# EvvGC_v1_2.net
KiCad netlist of a schematic drawn in Altium Designer
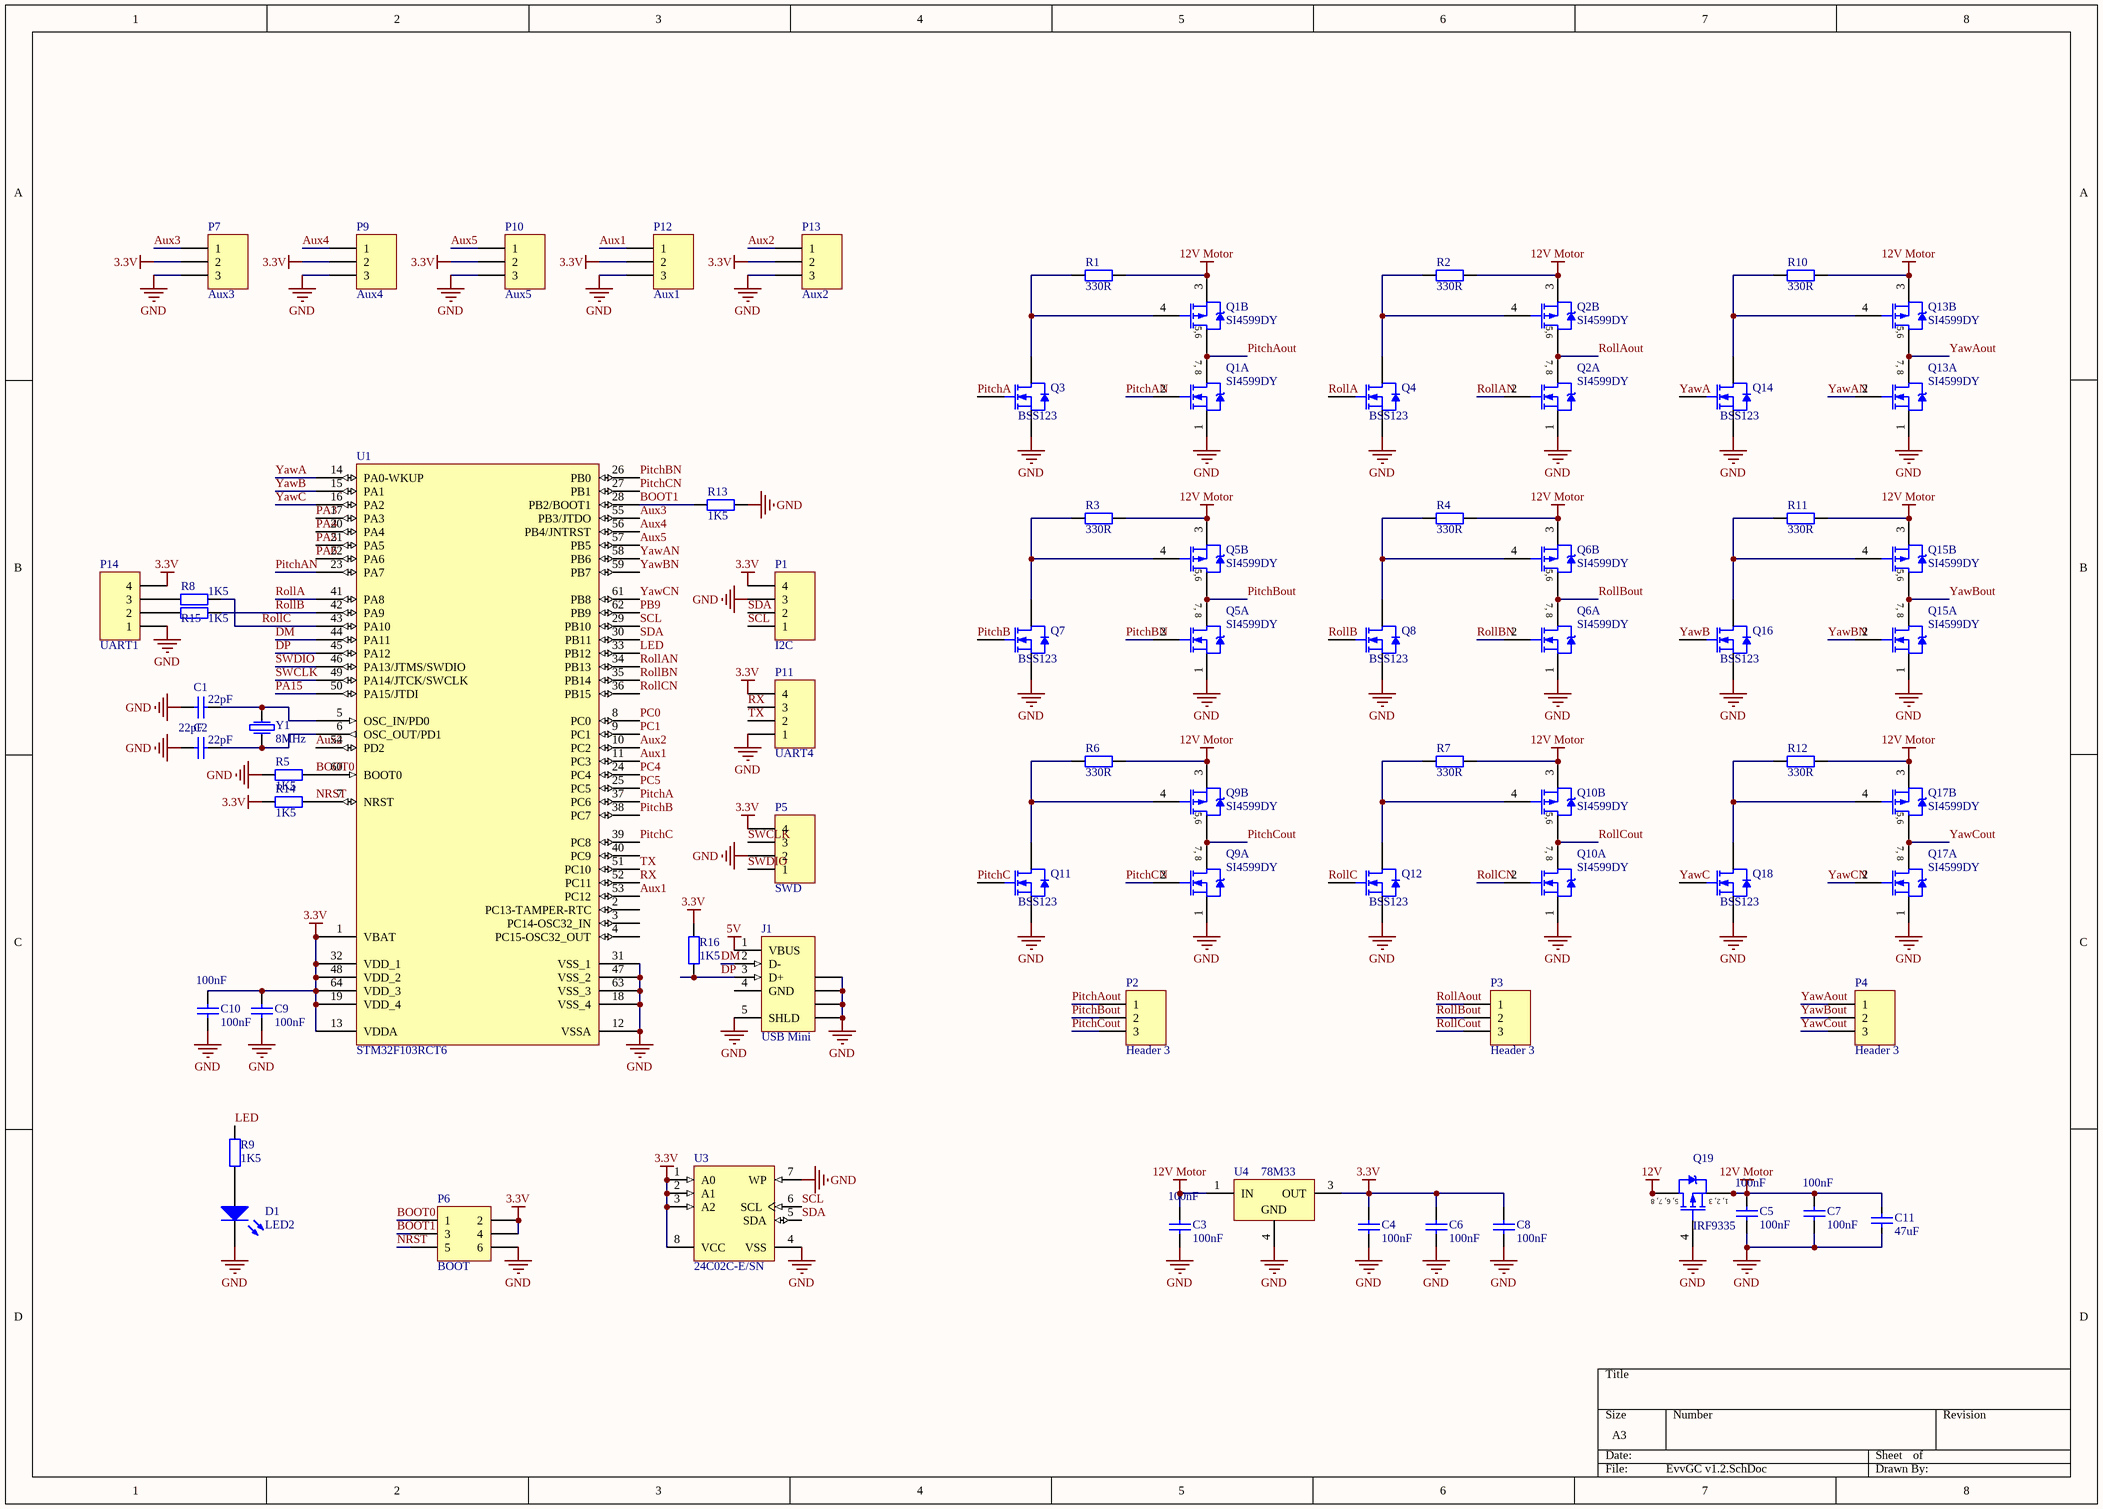
[diagram p0: EvvGC v1.2.SchDoc]

(export (version "E")
  (design (tool "Eeschema 10.0.6"))
  (components
    (comp (ref "C1")
      (value "22pF")
      (footprint "CAPC2012L")
      (description "Capacitor")
      (fields (field (name "PUBLISHER") "Altium Limited"))
      (libsource (lib "EMotus Components") (part "CAP0805"))
    )
    (comp (ref "C2")
      (value "22pF")
      (footprint "CAPC2012L")
      (description "Capacitor")
      (fields (field (name "ALTIUM_VALUE") "22pF") (field (name "PUBLISHER") "Altium Limited"))
      (libsource (lib "EMotus Components") (part "CAP0805"))
    )
    (comp (ref "C3")
      (value "100nF")
      (footprint "CAPC2012L")
      (description "Capacitor")
      (fields (field (name "ALTIUM_VALUE") "100nF") (field (name "PUBLISHER") "Altium Limited"))
      (libsource (lib "EMotus Components") (part "CAP0805"))
    )
    (comp (ref "C4")
      (value "100nF")
      (footprint "CAPC2012L")
      (description "Capacitor")
      (fields (field (name "PUBLISHER") "Altium Limited"))
      (libsource (lib "EMotus Components") (part "CAP0805"))
    )
    (comp (ref "C5")
      (value "100nF")
      (footprint "CAPC2012L")
      (description "Capacitor")
      (fields (field (name "ALTIUM_VALUE") "100nF") (field (name "PUBLISHER") "Altium Limited"))
      (libsource (lib "EMotus Components") (part "CAP0805"))
    )
    (comp (ref "C6")
      (value "100nF")
      (footprint "CAPC2012L")
      (description "Capacitor")
      (fields (field (name "PUBLISHER") "Altium Limited"))
      (libsource (lib "EMotus Components") (part "CAP0805"))
    )
    (comp (ref "C7")
      (value "100nF")
      (footprint "CAPC2012L")
      (description "Capacitor")
      (fields (field (name "ALTIUM_VALUE") "100nF") (field (name "PUBLISHER") "Altium Limited"))
      (libsource (lib "EMotus Components") (part "CAP0805"))
    )
    (comp (ref "C8")
      (value "100nF")
      (footprint "CAPC2012L")
      (description "Capacitor")
      (fields (field (name "PUBLISHER") "Altium Limited"))
      (libsource (lib "EMotus Components") (part "CAP0805"))
    )
    (comp (ref "C9")
      (value "100nF")
      (footprint "CAPC2012L")
      (description "Capacitor")
      (fields (field (name "PUBLISHER") "Altium Limited"))
      (libsource (lib "EMotus Components") (part "CAP0805"))
    )
    (comp (ref "C10")
      (value "100nF")
      (footprint "CAPC2012L")
      (description "Capacitor")
      (fields (field (name "ALTIUM_VALUE") "100nF") (field (name "PUBLISHER") "Altium Limited"))
      (libsource (lib "EMotus Components") (part "CAP0805"))
    )
    (comp (ref "C11")
      (value "47uF")
      (footprint "TC6032-2412")
      (description "Capacitor")
      (fields (field (name "PUBLISHER") "Altium Limited"))
      (libsource (lib "EMotus Components") (part "Cap"))
    )
    (comp (ref "D1")
      (value "LED2")
      (footprint "CAPC2012L")
      (description "Typical RED, GREEN, YELLOW, AMBER GaAs LED")
      (fields (field (name "PUBLISHER") "Altium Limited"))
      (libsource (lib "Miscellaneous Devices") (part "LED2"))
    )
    (comp (ref "J1")
      (value "USB Mini")
      (footprint "440247")
      (description "USB 2.0, Right Angle, SMT, B Type, Receptacle, 5 Position, Black")
      (fields (field (name "PUBLISHER") "Altium Limited"))
      (libsource (lib "AMP Serial Bus USB") (part "440247-2"))
    )
    (comp (ref "P1")
      (value "I2C")
      (footprint "HDR1X4")
      (description "Header, 4-Pin")
      (fields (field (name "PUBLISHER") "Altium Limited"))
      (libsource (lib "Miscellaneous Connectors") (part "Header 4"))
    )
    (comp (ref "P2")
      (value "Header 3")
      (footprint "HDR1X3")
      (description "Header, 3-Pin")
      (fields (field (name "PUBLISHER") "Altium Limited"))
      (libsource (lib "Miscellaneous Connectors") (part "Header 3"))
    )
    (comp (ref "P3")
      (value "Header 3")
      (footprint "HDR1X3")
      (description "Header, 3-Pin")
      (fields (field (name "PUBLISHER") "Altium Limited"))
      (libsource (lib "Miscellaneous Connectors") (part "Header 3"))
    )
    (comp (ref "P4")
      (value "Header 3")
      (footprint "HDR1X3")
      (description "Header, 3-Pin")
      (fields (field (name "PUBLISHER") "Altium Limited"))
      (libsource (lib "Miscellaneous Connectors") (part "Header 3"))
    )
    (comp (ref "P5")
      (value "SWD")
      (footprint "HDR1X4")
      (description "Header, 4-Pin")
      (fields (field (name "PUBLISHER") "Altium Limited"))
      (libsource (lib "Miscellaneous Connectors") (part "Header 4"))
    )
    (comp (ref "P6")
      (value "BOOT")
      (footprint "HDR2X3")
      (description "Header, 3-Pin, Dual row")
      (fields (field (name "PUBLISHER") "Altium Limited"))
      (libsource (lib "Miscellaneous Connectors") (part "Header 3X2"))
    )
    (comp (ref "P7")
      (value "Aux3")
      (footprint "HDR1X3")
      (description "Header, 3-Pin")
      (fields (field (name "PUBLISHER") "Altium Limited"))
      (libsource (lib "Miscellaneous Connectors") (part "Header 3"))
    )
    (comp (ref "P9")
      (value "Aux4")
      (footprint "HDR1X3")
      (description "Header, 3-Pin")
      (fields (field (name "PUBLISHER") "Altium Limited"))
      (libsource (lib "Miscellaneous Connectors") (part "Header 3"))
    )
    (comp (ref "P10")
      (value "Aux5")
      (footprint "HDR1X3")
      (description "Header, 3-Pin")
      (fields (field (name "PUBLISHER") "Altium Limited"))
      (libsource (lib "Miscellaneous Connectors") (part "Header 3"))
    )
    (comp (ref "P11")
      (value "UART4")
      (footprint "HDR1X4")
      (description "Header, 4-Pin")
      (fields (field (name "PUBLISHER") "Altium Limited"))
      (libsource (lib "Miscellaneous Connectors") (part "Header 4"))
    )
    (comp (ref "P12")
      (value "Aux1")
      (footprint "HDR1X3")
      (description "Header, 3-Pin")
      (fields (field (name "PUBLISHER") "Altium Limited"))
      (libsource (lib "Miscellaneous Connectors") (part "Header 3"))
    )
    (comp (ref "P13")
      (value "Aux2")
      (footprint "HDR1X3")
      (description "Header, 3-Pin")
      (fields (field (name "PUBLISHER") "Altium Limited"))
      (libsource (lib "Miscellaneous Connectors") (part "Header 3"))
    )
    (comp (ref "P14")
      (value "UART1")
      (footprint "HDR1X4")
      (description "Header, 4-Pin")
      (fields (field (name "PUBLISHER") "Altium Limited"))
      (libsource (lib "") (part "Header 4_1"))
    )
    (comp (ref "Q1")
      (value "SI4599DY")
      (footprint "SO-8_N")
      (description "HEXFET Power MOSFET")
      (fields (field (name "PUBLISHER") "Altium Limited"))
      (libsource (lib "VMU") (part "AUIRF7343"))
    )
    (comp (ref "Q2")
      (value "SI4599DY")
      (footprint "SO-8_N")
      (description "HEXFET Power MOSFET")
      (fields (field (name "PUBLISHER") "Altium Limited"))
      (libsource (lib "VMU") (part "AUIRF7343"))
    )
    (comp (ref "Q3")
      (value "BSS123")
      (footprint "SOT23_N_EM")
      (description "N-channel Enhancement Mode Field-effect Transistor")
      (fields (field (name "PUBLISHER") "Altium Limited"))
      (libsource (lib "EMotus Components") (part "2N7002"))
    )
    (comp (ref "Q4")
      (value "BSS123")
      (footprint "SOT23_N_EM")
      (description "N-channel Enhancement Mode Field-effect Transistor")
      (fields (field (name "PUBLISHER") "Altium Limited"))
      (libsource (lib "EMotus Components") (part "2N7002"))
    )
    (comp (ref "Q5")
      (value "SI4599DY")
      (footprint "SO-8_N")
      (description "HEXFET Power MOSFET")
      (fields (field (name "PUBLISHER") "Altium Limited"))
      (libsource (lib "VMU") (part "AUIRF7343"))
    )
    (comp (ref "Q6")
      (value "SI4599DY")
      (footprint "SO-8_N")
      (description "HEXFET Power MOSFET")
      (fields (field (name "PUBLISHER") "Altium Limited"))
      (libsource (lib "VMU") (part "AUIRF7343"))
    )
    (comp (ref "Q7")
      (value "BSS123")
      (footprint "SOT23_N_EM")
      (description "N-channel Enhancement Mode Field-effect Transistor")
      (fields (field (name "PUBLISHER") "Altium Limited"))
      (libsource (lib "EMotus Components") (part "2N7002"))
    )
    (comp (ref "Q8")
      (value "BSS123")
      (footprint "SOT23_N_EM")
      (description "N-channel Enhancement Mode Field-effect Transistor")
      (fields (field (name "PUBLISHER") "Altium Limited"))
      (libsource (lib "EMotus Components") (part "2N7002"))
    )
    (comp (ref "Q9")
      (value "SI4599DY")
      (footprint "SO-8_N")
      (description "HEXFET Power MOSFET")
      (fields (field (name "PUBLISHER") "Altium Limited"))
      (libsource (lib "VMU") (part "AUIRF7343"))
    )
    (comp (ref "Q10")
      (value "SI4599DY")
      (footprint "SO-8_N")
      (description "HEXFET Power MOSFET")
      (fields (field (name "PUBLISHER") "Altium Limited"))
      (libsource (lib "VMU") (part "AUIRF7343"))
    )
    (comp (ref "Q11")
      (value "BSS123")
      (footprint "SOT23_N_EM")
      (description "N-channel Enhancement Mode Field-effect Transistor")
      (fields (field (name "PUBLISHER") "Altium Limited"))
      (libsource (lib "EMotus Components") (part "2N7002"))
    )
    (comp (ref "Q12")
      (value "BSS123")
      (footprint "SOT23_N_EM")
      (description "N-channel Enhancement Mode Field-effect Transistor")
      (fields (field (name "PUBLISHER") "Altium Limited"))
      (libsource (lib "EMotus Components") (part "2N7002"))
    )
    (comp (ref "Q13")
      (value "SI4599DY")
      (footprint "SO-8_N")
      (description "HEXFET Power MOSFET")
      (fields (field (name "PUBLISHER") "Altium Limited"))
      (libsource (lib "VMU") (part "AUIRF7343"))
    )
    (comp (ref "Q14")
      (value "BSS123")
      (footprint "SOT23_N_EM")
      (description "N-channel Enhancement Mode Field-effect Transistor")
      (fields (field (name "PUBLISHER") "Altium Limited"))
      (libsource (lib "EMotus Components") (part "2N7002"))
    )
    (comp (ref "Q15")
      (value "SI4599DY")
      (footprint "SO-8_N")
      (description "HEXFET Power MOSFET")
      (fields (field (name "PUBLISHER") "Altium Limited"))
      (libsource (lib "VMU") (part "AUIRF7343"))
    )
    (comp (ref "Q16")
      (value "BSS123")
      (footprint "SOT23_N_EM")
      (description "N-channel Enhancement Mode Field-effect Transistor")
      (fields (field (name "PUBLISHER") "Altium Limited"))
      (libsource (lib "EMotus Components") (part "2N7002"))
    )
    (comp (ref "Q17")
      (value "SI4599DY")
      (footprint "SO-8_N")
      (description "HEXFET Power MOSFET")
      (fields (field (name "PUBLISHER") "Altium Limited"))
      (libsource (lib "VMU") (part "AUIRF7343"))
    )
    (comp (ref "Q18")
      (value "BSS123")
      (footprint "SOT23_N_EM")
      (description "N-channel Enhancement Mode Field-effect Transistor")
      (fields (field (name "PUBLISHER") "Altium Limited"))
      (libsource (lib "EMotus Components") (part "2N7002"))
    )
    (comp (ref "Q19")
      (value "IRF9335")
      (footprint "SO-8_N")
      (description "HEXFET Power MOSFET")
      (fields
        (field (name "MANUFACTURER") "International Rectifier")
        (field (name "PART NUMBER") "IRF9335PBF")
        (field (name "PUBLISHER") "Altium Limited")
      )
      (libsource (lib "IR Discrete MOSFET - Power") (part "IRF7404"))
    )
    (comp (ref "R1")
      (value "330R")
      (footprint "C0805")
      (description "Resistor")
      (fields (field (name "PUBLISHER") "Altium Limited"))
      (libsource (lib "My Altium Lib") (part "Res"))
    )
    (comp (ref "R2")
      (value "330R")
      (footprint "C0805")
      (description "Resistor")
      (fields (field (name "PUBLISHER") "Altium Limited"))
      (libsource (lib "My Altium Lib") (part "Res"))
    )
    (comp (ref "R3")
      (value "330R")
      (footprint "C0805")
      (description "Resistor")
      (fields (field (name "PUBLISHER") "Altium Limited"))
      (libsource (lib "My Altium Lib") (part "Res"))
    )
    (comp (ref "R4")
      (value "330R")
      (footprint "C0805")
      (description "Resistor")
      (fields (field (name "PUBLISHER") "Altium Limited"))
      (libsource (lib "My Altium Lib") (part "Res"))
    )
    (comp (ref "R5")
      (value "1K5")
      (footprint "RESC1608N")
      (description "RES 0603 1K5")
      (fields (field (name "TOLERANCE") "±5%"))
      (libsource (lib "Resistors") (part "RES 0603 330R"))
    )
    (comp (ref "R6")
      (value "330R")
      (footprint "C0805")
      (description "Resistor")
      (fields (field (name "PUBLISHER") "Altium Limited"))
      (libsource (lib "My Altium Lib") (part "Res"))
    )
    (comp (ref "R7")
      (value "330R")
      (footprint "C0805")
      (description "Resistor")
      (fields (field (name "PUBLISHER") "Altium Limited"))
      (libsource (lib "My Altium Lib") (part "Res"))
    )
    (comp (ref "R8")
      (value "1K5")
      (footprint "RESC1608N")
      (description "RES 0603 1K5")
      (fields (field (name "TOLERANCE") "±5%"))
      (libsource (lib "Resistors") (part "RES 0603 330R"))
    )
    (comp (ref "R9")
      (value "1K5")
      (footprint "RESC1608N")
      (description "RES 0603 1K5")
      (fields (field (name "TOLERANCE") "±5%"))
      (libsource (lib "") (part "RES 0603 330R_1"))
    )
    (comp (ref "R10")
      (value "330R")
      (footprint "C0805")
      (description "Resistor")
      (fields (field (name "PUBLISHER") "Altium Limited"))
      (libsource (lib "My Altium Lib") (part "Res"))
    )
    (comp (ref "R11")
      (value "330R")
      (footprint "C0805")
      (description "Resistor")
      (fields (field (name "PUBLISHER") "Altium Limited"))
      (libsource (lib "My Altium Lib") (part "Res"))
    )
    (comp (ref "R12")
      (value "330R")
      (footprint "C0805")
      (description "Resistor")
      (fields (field (name "PUBLISHER") "Altium Limited"))
      (libsource (lib "My Altium Lib") (part "Res"))
    )
    (comp (ref "R13")
      (value "1K5")
      (footprint "RESC1608N")
      (description "RES 0603 1K5")
      (fields (field (name "TOLERANCE") "±5%"))
      (libsource (lib "Resistors") (part "RES 0603 330R"))
    )
    (comp (ref "R14")
      (value "1K5")
      (footprint "RESC1608N")
      (description "RES 0603 1K5")
      (fields (field (name "TOLERANCE") "±5%"))
      (libsource (lib "Resistors") (part "RES 0603 330R"))
    )
    (comp (ref "R15")
      (value "1K5")
      (footprint "RESC1608N")
      (description "RES 0603 1K5")
      (fields (field (name "TOLERANCE") "±5%"))
      (libsource (lib "Resistors") (part "RES 0603 330R"))
    )
    (comp (ref "R16")
      (value "1K5")
      (footprint "RESC1608N")
      (description "RES 0603 1K5")
      (fields (field (name "TOLERANCE") "±5%"))
      (libsource (lib "") (part "RES 0603 330R_1"))
    )
    (comp (ref "U1")
      (value "STM32F103RCT6")
      (footprint "LQFP64_N")
      (description "STM32 ARM-based 32-bit MCU with 128 Kbytes Flash, 64-pin LQFP, Industrial Temperature")
      (fields (field (name "PUBLISHER") "Altium Limited"))
      (libsource (lib "ST Microcontroller 32-Bit STM32") (part "STM32F103RBT6"))
    )
    (comp (ref "U3")
      (value "24C02C-E/SN")
      (footprint "SOIC-SN8_N")
      (description "2Kbit, 400kHz, 5V, I2C Serial EEPROM, 8-Pin SOIC 150mil, Extended Temperature")
      (fields (field (name "PUBLISHER") "Altium Limited"))
      (libsource (lib "Microchip EEPROM I2C Serial") (part "24C02C-E/SN"))
    )
    (comp (ref "U4")
      (value "78M33")
      (footprint "TO-252")
      (description "Positive Voltage Regulator")
      (fields (field (name "PUBLISHER") "Altium Limited"))
      (libsource (lib "SMART LIB") (part "L78M05CDT"))
    )
    (comp (ref "Y1")
      (value "8MHz")
      (footprint "ABM3")
      (description "CRYSTAL 16M SMD5x3.2mm")
      (fields (field (name "MANUFACTURER") "ABRACON") (field (name "FARNELL PART NUMBER") "1611806"))
      (libsource (lib "elektromotus") (part "CRYSTAL 16M SMD5x3.2mm"))
    )
  )
  (nets
    (net (code "1") (name "/Aux1") (class "Default")
      (node (ref "P12") (pin "1") (pinfunction "1_1") (pintype "passive"))
      (node (ref "U1") (pin "11") (pinfunction "PC3_11") (pintype "bidirectional"))
      (node (ref "U1") (pin "53") (pinfunction "PC12_53") (pintype "bidirectional"))
    )
    (net (code "2") (name "/Aux2") (class "Default")
      (node (ref "P13") (pin "1") (pinfunction "1_1") (pintype "passive"))
      (node (ref "U1") (pin "10") (pinfunction "PC2_10") (pintype "bidirectional"))
      (node (ref "U1") (pin "54") (pinfunction "PD2_54") (pintype "bidirectional"))
    )
    (net (code "3") (name "/Aux3") (class "Default")
      (node (ref "P7") (pin "1") (pinfunction "1_1") (pintype "passive"))
      (node (ref "U1") (pin "55") (pinfunction "PB3/JTDO_55") (pintype "bidirectional"))
    )
    (net (code "4") (name "/Aux4") (class "Default")
      (node (ref "P9") (pin "1") (pinfunction "1_1") (pintype "passive"))
      (node (ref "U1") (pin "56") (pinfunction "PB4/JNTRST_56") (pintype "bidirectional"))
    )
    (net (code "5") (name "/Aux5") (class "Default")
      (node (ref "P10") (pin "1") (pinfunction "1_1") (pintype "passive"))
      (node (ref "U1") (pin "57") (pinfunction "PB5_57") (pintype "bidirectional"))
    )
    (net (code "6") (name "/BOOT0") (class "Default")
      (node (ref "P6") (pin "1") (pinfunction "1_1") (pintype "passive"))
      (node (ref "R5") (pin "1") (pinfunction "1_1") (pintype "passive"))
      (node (ref "U1") (pin "60") (pinfunction "BOOT0_60") (pintype "input"))
    )
    (net (code "7") (name "/BOOT1") (class "Default")
      (node (ref "P6") (pin "3") (pinfunction "3_3") (pintype "passive"))
      (node (ref "R13") (pin "2") (pinfunction "2_2") (pintype "passive"))
      (node (ref "U1") (pin "28") (pinfunction "PB2/BOOT1_28") (pintype "bidirectional"))
    )
    (net (code "8") (name "/DM") (class "Default")
      (node (ref "J1") (pin "2") (pinfunction "D-_2") (pintype "input"))
      (node (ref "U1") (pin "44") (pinfunction "PA11_44") (pintype "bidirectional"))
    )
    (net (code "9") (name "/DP") (class "Default")
      (node (ref "J1") (pin "3") (pinfunction "D+_3") (pintype "input"))
      (node (ref "R16") (pin "2") (pinfunction "2_2") (pintype "passive"))
      (node (ref "U1") (pin "45") (pinfunction "PA12_45") (pintype "bidirectional"))
    )
    (net (code "10") (name "/LED") (class "Default")
      (node (ref "R9") (pin "1") (pinfunction "1_1") (pintype "passive"))
      (node (ref "U1") (pin "33") (pinfunction "PB12_33") (pintype "bidirectional"))
    )
    (net (code "11") (name "/NRST") (class "Default")
      (node (ref "P6") (pin "5") (pinfunction "5_5") (pintype "passive"))
      (node (ref "R14") (pin "1") (pinfunction "1_1") (pintype "passive"))
      (node (ref "U1") (pin "7") (pinfunction "NRST_7") (pintype "bidirectional"))
    )
    (net (code "12") (name "/PA3") (class "Default")
      (node (ref "U1") (pin "17") (pinfunction "PA3_17") (pintype "bidirectional"))
    )
    (net (code "13") (name "/PA4") (class "Default")
      (node (ref "U1") (pin "20") (pinfunction "PA4_20") (pintype "bidirectional"))
    )
    (net (code "14") (name "/PA5") (class "Default")
      (node (ref "U1") (pin "21") (pinfunction "PA5_21") (pintype "bidirectional"))
    )
    (net (code "15") (name "/PA6") (class "Default")
      (node (ref "U1") (pin "22") (pinfunction "PA6_22") (pintype "bidirectional"))
    )
    (net (code "16") (name "/PA15") (class "Default")
      (node (ref "U1") (pin "50") (pinfunction "PA15/JTDI_50") (pintype "bidirectional"))
    )
    (net (code "17") (name "/PB9") (class "Default")
      (node (ref "U1") (pin "62") (pinfunction "PB9_62") (pintype "bidirectional"))
    )
    (net (code "18") (name "/PC0") (class "Default")
      (node (ref "U1") (pin "8") (pinfunction "PC0_8") (pintype "bidirectional"))
    )
    (net (code "19") (name "/PC1") (class "Default")
      (node (ref "U1") (pin "9") (pinfunction "PC1_9") (pintype "bidirectional"))
    )
    (net (code "20") (name "/PC4") (class "Default")
      (node (ref "U1") (pin "24") (pinfunction "PC4_24") (pintype "bidirectional"))
    )
    (net (code "21") (name "/PC5") (class "Default")
      (node (ref "U1") (pin "25") (pinfunction "PC5_25") (pintype "bidirectional"))
    )
    (net (code "22") (name "/PitchA") (class "Default")
      (node (ref "Q3") (pin "1") (pinfunction "G_1") (pintype "passive"))
      (node (ref "U1") (pin "37") (pinfunction "PC6_37") (pintype "bidirectional"))
    )
    (net (code "23") (name "/PitchAN") (class "Default")
      (node (ref "Q1") (pin "2") (pinfunction "G1_2") (pintype "passive"))
      (node (ref "U1") (pin "23") (pinfunction "PA7_23") (pintype "bidirectional"))
    )
    (net (code "24") (name "/PitchAout") (class "Default")
      (node (ref "P2") (pin "1") (pinfunction "1_1") (pintype "passive"))
      (node (ref "Q1") (pin "5") (pinfunction "D2_5") (pintype "passive"))
      (node (ref "Q1") (pin "6") (pinfunction "D2_6") (pintype "passive"))
      (node (ref "Q1") (pin "7") (pinfunction "D1_7") (pintype "passive"))
      (node (ref "Q1") (pin "8") (pinfunction "D1_8") (pintype "passive"))
    )
    (net (code "25") (name "/PitchB") (class "Default")
      (node (ref "Q7") (pin "1") (pinfunction "G_1") (pintype "passive"))
      (node (ref "U1") (pin "38") (pinfunction "PC7_38") (pintype "bidirectional"))
    )
    (net (code "26") (name "/PitchBN") (class "Default")
      (node (ref "Q5") (pin "2") (pinfunction "G1_2") (pintype "passive"))
      (node (ref "U1") (pin "26") (pinfunction "PB0_26") (pintype "bidirectional"))
    )
    (net (code "27") (name "/PitchBout") (class "Default")
      (node (ref "P2") (pin "2") (pinfunction "2_2") (pintype "passive"))
      (node (ref "Q5") (pin "5") (pinfunction "D2_5") (pintype "passive"))
      (node (ref "Q5") (pin "6") (pinfunction "D2_6") (pintype "passive"))
      (node (ref "Q5") (pin "7") (pinfunction "D1_7") (pintype "passive"))
      (node (ref "Q5") (pin "8") (pinfunction "D1_8") (pintype "passive"))
    )
    (net (code "28") (name "/PitchC") (class "Default")
      (node (ref "Q11") (pin "1") (pinfunction "G_1") (pintype "passive"))
      (node (ref "U1") (pin "39") (pinfunction "PC8_39") (pintype "bidirectional"))
    )
    (net (code "29") (name "/PitchCN") (class "Default")
      (node (ref "Q9") (pin "2") (pinfunction "G1_2") (pintype "passive"))
      (node (ref "U1") (pin "27") (pinfunction "PB1_27") (pintype "bidirectional"))
    )
    (net (code "30") (name "/PitchCout") (class "Default")
      (node (ref "P2") (pin "3") (pinfunction "3_3") (pintype "passive"))
      (node (ref "Q9") (pin "5") (pinfunction "D2_5") (pintype "passive"))
      (node (ref "Q9") (pin "6") (pinfunction "D2_6") (pintype "passive"))
      (node (ref "Q9") (pin "7") (pinfunction "D1_7") (pintype "passive"))
      (node (ref "Q9") (pin "8") (pinfunction "D1_8") (pintype "passive"))
    )
    (net (code "31") (name "/RX") (class "Default")
      (node (ref "P11") (pin "3") (pinfunction "3_3") (pintype "passive"))
      (node (ref "U1") (pin "52") (pinfunction "PC11_52") (pintype "bidirectional"))
    )
    (net (code "32") (name "/RollA") (class "Default")
      (node (ref "Q4") (pin "1") (pinfunction "G_1") (pintype "passive"))
      (node (ref "U1") (pin "41") (pinfunction "PA8_41") (pintype "bidirectional"))
    )
    (net (code "33") (name "/RollAN") (class "Default")
      (node (ref "Q2") (pin "2") (pinfunction "G1_2") (pintype "passive"))
      (node (ref "U1") (pin "34") (pinfunction "PB13_34") (pintype "bidirectional"))
    )
    (net (code "34") (name "/RollAout") (class "Default")
      (node (ref "P3") (pin "1") (pinfunction "1_1") (pintype "passive"))
      (node (ref "Q2") (pin "5") (pinfunction "D2_5") (pintype "passive"))
      (node (ref "Q2") (pin "6") (pinfunction "D2_6") (pintype "passive"))
      (node (ref "Q2") (pin "7") (pinfunction "D1_7") (pintype "passive"))
      (node (ref "Q2") (pin "8") (pinfunction "D1_8") (pintype "passive"))
    )
    (net (code "35") (name "/RollB") (class "Default")
      (node (ref "Q8") (pin "1") (pinfunction "G_1") (pintype "passive"))
      (node (ref "R15") (pin "1") (pinfunction "1_1") (pintype "passive"))
      (node (ref "U1") (pin "42") (pinfunction "PA9_42") (pintype "bidirectional"))
    )
    (net (code "36") (name "/RollBN") (class "Default")
      (node (ref "Q6") (pin "2") (pinfunction "G1_2") (pintype "passive"))
      (node (ref "U1") (pin "35") (pinfunction "PB14_35") (pintype "bidirectional"))
    )
    (net (code "37") (name "/RollBout") (class "Default")
      (node (ref "P3") (pin "2") (pinfunction "2_2") (pintype "passive"))
      (node (ref "Q6") (pin "5") (pinfunction "D2_5") (pintype "passive"))
      (node (ref "Q6") (pin "6") (pinfunction "D2_6") (pintype "passive"))
      (node (ref "Q6") (pin "7") (pinfunction "D1_7") (pintype "passive"))
      (node (ref "Q6") (pin "8") (pinfunction "D1_8") (pintype "passive"))
    )
    (net (code "38") (name "/RollC") (class "Default")
      (node (ref "Q12") (pin "1") (pinfunction "G_1") (pintype "passive"))
      (node (ref "R8") (pin "1") (pinfunction "1_1") (pintype "passive"))
      (node (ref "U1") (pin "43") (pinfunction "PA10_43") (pintype "bidirectional"))
    )
    (net (code "39") (name "/RollCN") (class "Default")
      (node (ref "Q10") (pin "2") (pinfunction "G1_2") (pintype "passive"))
      (node (ref "U1") (pin "36") (pinfunction "PB15_36") (pintype "bidirectional"))
    )
    (net (code "40") (name "/RollCout") (class "Default")
      (node (ref "P3") (pin "3") (pinfunction "3_3") (pintype "passive"))
      (node (ref "Q10") (pin "5") (pinfunction "D2_5") (pintype "passive"))
      (node (ref "Q10") (pin "6") (pinfunction "D2_6") (pintype "passive"))
      (node (ref "Q10") (pin "7") (pinfunction "D1_7") (pintype "passive"))
      (node (ref "Q10") (pin "8") (pinfunction "D1_8") (pintype "passive"))
    )
    (net (code "41") (name "/SCL") (class "Default")
      (node (ref "P1") (pin "1") (pinfunction "1_1") (pintype "passive"))
      (node (ref "U1") (pin "29") (pinfunction "PB10_29") (pintype "bidirectional"))
      (node (ref "U3") (pin "6") (pinfunction "SCL_6") (pintype "input"))
    )
    (net (code "42") (name "/SDA") (class "Default")
      (node (ref "P1") (pin "2") (pinfunction "2_2") (pintype "passive"))
      (node (ref "U1") (pin "30") (pinfunction "PB11_30") (pintype "bidirectional"))
      (node (ref "U3") (pin "5") (pinfunction "SDA_5") (pintype "bidirectional"))
    )
    (net (code "43") (name "/SWCLK") (class "Default")
      (node (ref "P5") (pin "3") (pinfunction "3_3") (pintype "passive"))
      (node (ref "U1") (pin "49") (pinfunction "PA14/JTCK/SWCLK_49") (pintype "bidirectional"))
    )
    (net (code "44") (name "/SWDIO") (class "Default")
      (node (ref "P5") (pin "1") (pinfunction "1_1") (pintype "passive"))
      (node (ref "U1") (pin "46") (pinfunction "PA13/JTMS/SWDIO_46") (pintype "bidirectional"))
    )
    (net (code "45") (name "/TX") (class "Default")
      (node (ref "P11") (pin "2") (pinfunction "2_2") (pintype "passive"))
      (node (ref "U1") (pin "51") (pinfunction "PC10_51") (pintype "bidirectional"))
    )
    (net (code "46") (name "/YawA") (class "Default")
      (node (ref "Q14") (pin "1") (pinfunction "G_1") (pintype "passive"))
      (node (ref "U1") (pin "14") (pinfunction "PA0-WKUP_14") (pintype "bidirectional"))
    )
    (net (code "47") (name "/YawAN") (class "Default")
      (node (ref "Q13") (pin "2") (pinfunction "G1_2") (pintype "passive"))
      (node (ref "U1") (pin "58") (pinfunction "PB6_58") (pintype "bidirectional"))
    )
    (net (code "48") (name "/YawAout") (class "Default")
      (node (ref "P4") (pin "1") (pinfunction "1_1") (pintype "passive"))
      (node (ref "Q13") (pin "5") (pinfunction "D2_5") (pintype "passive"))
      (node (ref "Q13") (pin "6") (pinfunction "D2_6") (pintype "passive"))
      (node (ref "Q13") (pin "7") (pinfunction "D1_7") (pintype "passive"))
      (node (ref "Q13") (pin "8") (pinfunction "D1_8") (pintype "passive"))
    )
    (net (code "49") (name "/YawB") (class "Default")
      (node (ref "Q16") (pin "1") (pinfunction "G_1") (pintype "passive"))
      (node (ref "U1") (pin "15") (pinfunction "PA1_15") (pintype "bidirectional"))
    )
    (net (code "50") (name "/YawBN") (class "Default")
      (node (ref "Q15") (pin "2") (pinfunction "G1_2") (pintype "passive"))
      (node (ref "U1") (pin "59") (pinfunction "PB7_59") (pintype "bidirectional"))
    )
    (net (code "51") (name "/YawBout") (class "Default")
      (node (ref "P4") (pin "2") (pinfunction "2_2") (pintype "passive"))
      (node (ref "Q15") (pin "5") (pinfunction "D2_5") (pintype "passive"))
      (node (ref "Q15") (pin "6") (pinfunction "D2_6") (pintype "passive"))
      (node (ref "Q15") (pin "7") (pinfunction "D1_7") (pintype "passive"))
      (node (ref "Q15") (pin "8") (pinfunction "D1_8") (pintype "passive"))
    )
    (net (code "52") (name "/YawC") (class "Default")
      (node (ref "Q18") (pin "1") (pinfunction "G_1") (pintype "passive"))
      (node (ref "U1") (pin "16") (pinfunction "PA2_16") (pintype "bidirectional"))
    )
    (net (code "53") (name "/YawCN") (class "Default")
      (node (ref "Q17") (pin "2") (pinfunction "G1_2") (pintype "passive"))
      (node (ref "U1") (pin "61") (pinfunction "PB8_61") (pintype "bidirectional"))
    )
    (net (code "54") (name "/YawCout") (class "Default")
      (node (ref "P4") (pin "3") (pinfunction "3_3") (pintype "passive"))
      (node (ref "Q17") (pin "5") (pinfunction "D2_5") (pintype "passive"))
      (node (ref "Q17") (pin "6") (pinfunction "D2_6") (pintype "passive"))
      (node (ref "Q17") (pin "7") (pinfunction "D1_7") (pintype "passive"))
      (node (ref "Q17") (pin "8") (pinfunction "D1_8") (pintype "passive"))
    )
    (net (code "55") (name "3.3V") (class "Default")
      (node (ref "C10") (pin "1") (pinfunction "1_1") (pintype "passive"))
      (node (ref "C4") (pin "1") (pinfunction "1_1") (pintype "passive"))
      (node (ref "C6") (pin "1") (pinfunction "1_1") (pintype "passive"))
      (node (ref "C8") (pin "1") (pinfunction "1_1") (pintype "passive"))
      (node (ref "C9") (pin "1") (pinfunction "1_1") (pintype "passive"))
      (node (ref "P1") (pin "4") (pinfunction "4_4") (pintype "passive"))
      (node (ref "P10") (pin "2") (pinfunction "2_2") (pintype "passive"))
      (node (ref "P11") (pin "4") (pinfunction "4_4") (pintype "passive"))
      (node (ref "P12") (pin "2") (pinfunction "2_2") (pintype "passive"))
      (node (ref "P13") (pin "2") (pinfunction "2_2") (pintype "passive"))
      (node (ref "P14") (pin "4") (pinfunction "4_4") (pintype "passive"))
      (node (ref "P5") (pin "4") (pinfunction "4_4") (pintype "passive"))
      (node (ref "P6") (pin "2") (pinfunction "2_2") (pintype "passive"))
      (node (ref "P6") (pin "4") (pinfunction "4_4") (pintype "passive"))
      (node (ref "P7") (pin "2") (pinfunction "2_2") (pintype "passive"))
      (node (ref "P9") (pin "2") (pinfunction "2_2") (pintype "passive"))
      (node (ref "R14") (pin "2") (pinfunction "2_2") (pintype "passive"))
      (node (ref "R16") (pin "1") (pinfunction "1_1") (pintype "passive"))
      (node (ref "U1") (pin "1") (pinfunction "VBAT_1") (pintype "power_in"))
      (node (ref "U1") (pin "13") (pinfunction "VDDA_13") (pintype "power_in"))
      (node (ref "U1") (pin "19") (pinfunction "VDD_4_19") (pintype "power_in"))
      (node (ref "U1") (pin "32") (pinfunction "VDD_1_32") (pintype "power_in"))
      (node (ref "U1") (pin "48") (pinfunction "VDD_2_48") (pintype "power_in"))
      (node (ref "U1") (pin "64") (pinfunction "VDD_3_64") (pintype "power_in"))
      (node (ref "U3") (pin "1") (pinfunction "A0_1") (pintype "input"))
      (node (ref "U3") (pin "2") (pinfunction "A1_2") (pintype "input"))
      (node (ref "U3") (pin "3") (pinfunction "A2_3") (pintype "input"))
      (node (ref "U3") (pin "8") (pinfunction "VCC_8") (pintype "power_in"))
      (node (ref "U4") (pin "3") (pinfunction "OUT_3") (pintype "power_in"))
    )
    (net (code "56") (name "5V") (class "Default")
      (node (ref "J1") (pin "1") (pinfunction "VBUS_1") (pintype "power_in"))
    )
    (net (code "57") (name "12V") (class "Default")
      (node (ref "Q19") (pin "5") (pinfunction "D_5") (pintype "passive"))
      (node (ref "Q19") (pin "6") (pinfunction "D_6") (pintype "passive"))
      (node (ref "Q19") (pin "7") (pinfunction "D_7") (pintype "passive"))
      (node (ref "Q19") (pin "8") (pinfunction "D_8") (pintype "passive"))
    )
    (net (code "58") (name "12V Motor") (class "Default")
      (node (ref "C11") (pin "2") (pinfunction "2_2") (pintype "passive"))
      (node (ref "C3") (pin "1") (pinfunction "1_1") (pintype "passive"))
      (node (ref "C5") (pin "1") (pinfunction "1_1") (pintype "passive"))
      (node (ref "C7") (pin "1") (pinfunction "1_1") (pintype "passive"))
      (node (ref "Q1") (pin "3") (pinfunction "S2_3") (pintype "passive"))
      (node (ref "Q10") (pin "3") (pinfunction "S2_3") (pintype "passive"))
      (node (ref "Q13") (pin "3") (pinfunction "S2_3") (pintype "passive"))
      (node (ref "Q15") (pin "3") (pinfunction "S2_3") (pintype "passive"))
      (node (ref "Q17") (pin "3") (pinfunction "S2_3") (pintype "passive"))
      (node (ref "Q19") (pin "1") (pinfunction "S_1") (pintype "passive"))
      (node (ref "Q19") (pin "2") (pinfunction "S_2") (pintype "passive"))
      (node (ref "Q19") (pin "3") (pinfunction "S_3") (pintype "passive"))
      (node (ref "Q2") (pin "3") (pinfunction "S2_3") (pintype "passive"))
      (node (ref "Q5") (pin "3") (pinfunction "S2_3") (pintype "passive"))
      (node (ref "Q6") (pin "3") (pinfunction "S2_3") (pintype "passive"))
      (node (ref "Q9") (pin "3") (pinfunction "S2_3") (pintype "passive"))
      (node (ref "R1") (pin "2") (pinfunction "2_2") (pintype "passive"))
      (node (ref "R10") (pin "2") (pinfunction "2_2") (pintype "passive"))
      (node (ref "R11") (pin "2") (pinfunction "2_2") (pintype "passive"))
      (node (ref "R12") (pin "2") (pinfunction "2_2") (pintype "passive"))
      (node (ref "R2") (pin "2") (pinfunction "2_2") (pintype "passive"))
      (node (ref "R3") (pin "2") (pinfunction "2_2") (pintype "passive"))
      (node (ref "R4") (pin "2") (pinfunction "2_2") (pintype "passive"))
      (node (ref "R6") (pin "2") (pinfunction "2_2") (pintype "passive"))
      (node (ref "R7") (pin "2") (pinfunction "2_2") (pintype "passive"))
      (node (ref "U4") (pin "1") (pinfunction "IN_1") (pintype "power_in"))
    )
    (net (code "59") (name "GND") (class "Default")
      (node (ref "C1") (pin "2") (pinfunction "2_2") (pintype "passive"))
      (node (ref "C10") (pin "2") (pinfunction "2_2") (pintype "passive"))
      (node (ref "C11") (pin "1") (pinfunction "1_1") (pintype "passive"))
      (node (ref "C2") (pin "2") (pinfunction "2_2") (pintype "passive"))
      (node (ref "C3") (pin "2") (pinfunction "2_2") (pintype "passive"))
      (node (ref "C4") (pin "2") (pinfunction "2_2") (pintype "passive"))
      (node (ref "C5") (pin "2") (pinfunction "2_2") (pintype "passive"))
      (node (ref "C6") (pin "2") (pinfunction "2_2") (pintype "passive"))
      (node (ref "C7") (pin "2") (pinfunction "2_2") (pintype "passive"))
      (node (ref "C8") (pin "2") (pinfunction "2_2") (pintype "passive"))
      (node (ref "C9") (pin "2") (pinfunction "2_2") (pintype "passive"))
      (node (ref "D1") (pin "2") (pinfunction "K_2") (pintype "passive"))
      (node (ref "J1") (pin "5") (pinfunction "SHLD_5") (pintype "passive"))
      (node (ref "J1") (pin "6") (pinfunction "SHLD_6") (pintype "passive"))
      (node (ref "J1") (pin "7") (pinfunction "SHLD_7") (pintype "passive"))
      (node (ref "J1") (pin "8") (pinfunction "SHLD_8") (pintype "passive"))
      (node (ref "J1") (pin "9") (pinfunction "SHLD_9") (pintype "passive"))
      (node (ref "P1") (pin "3") (pinfunction "3_3") (pintype "passive"))
      (node (ref "P10") (pin "3") (pinfunction "3_3") (pintype "passive"))
      (node (ref "P11") (pin "1") (pinfunction "1_1") (pintype "passive"))
      (node (ref "P12") (pin "3") (pinfunction "3_3") (pintype "passive"))
      (node (ref "P13") (pin "3") (pinfunction "3_3") (pintype "passive"))
      (node (ref "P14") (pin "1") (pinfunction "1_1") (pintype "passive"))
      (node (ref "P5") (pin "2") (pinfunction "2_2") (pintype "passive"))
      (node (ref "P6") (pin "6") (pinfunction "6_6") (pintype "passive"))
      (node (ref "P7") (pin "3") (pinfunction "3_3") (pintype "passive"))
      (node (ref "P9") (pin "3") (pinfunction "3_3") (pintype "passive"))
      (node (ref "Q1") (pin "1") (pinfunction "S1_1") (pintype "passive"))
      (node (ref "Q10") (pin "1") (pinfunction "S1_1") (pintype "passive"))
      (node (ref "Q11") (pin "2") (pinfunction "S_2") (pintype "passive"))
      (node (ref "Q12") (pin "2") (pinfunction "S_2") (pintype "passive"))
      (node (ref "Q13") (pin "1") (pinfunction "S1_1") (pintype "passive"))
      (node (ref "Q14") (pin "2") (pinfunction "S_2") (pintype "passive"))
      (node (ref "Q15") (pin "1") (pinfunction "S1_1") (pintype "passive"))
      (node (ref "Q16") (pin "2") (pinfunction "S_2") (pintype "passive"))
      (node (ref "Q17") (pin "1") (pinfunction "S1_1") (pintype "passive"))
      (node (ref "Q18") (pin "2") (pinfunction "S_2") (pintype "passive"))
      (node (ref "Q19") (pin "4") (pinfunction "G_4") (pintype "passive"))
      (node (ref "Q2") (pin "1") (pinfunction "S1_1") (pintype "passive"))
      (node (ref "Q3") (pin "2") (pinfunction "S_2") (pintype "passive"))
      (node (ref "Q4") (pin "2") (pinfunction "S_2") (pintype "passive"))
      (node (ref "Q5") (pin "1") (pinfunction "S1_1") (pintype "passive"))
      (node (ref "Q6") (pin "1") (pinfunction "S1_1") (pintype "passive"))
      (node (ref "Q7") (pin "2") (pinfunction "S_2") (pintype "passive"))
      (node (ref "Q8") (pin "2") (pinfunction "S_2") (pintype "passive"))
      (node (ref "Q9") (pin "1") (pinfunction "S1_1") (pintype "passive"))
      (node (ref "R13") (pin "1") (pinfunction "1_1") (pintype "passive"))
      (node (ref "R5") (pin "2") (pinfunction "2_2") (pintype "passive"))
      (node (ref "U1") (pin "12") (pinfunction "VSSA_12") (pintype "power_in"))
      (node (ref "U1") (pin "18") (pinfunction "VSS_4_18") (pintype "power_in"))
      (node (ref "U1") (pin "31") (pinfunction "VSS_1_31") (pintype "power_in"))
      (node (ref "U1") (pin "47") (pinfunction "VSS_2_47") (pintype "power_in"))
      (node (ref "U1") (pin "63") (pinfunction "VSS_3_63") (pintype "power_in"))
      (node (ref "U3") (pin "4") (pinfunction "VSS_4") (pintype "power_in"))
      (node (ref "U3") (pin "7") (pinfunction "WP_7") (pintype "input"))
      (node (ref "U4") (pin "4") (pinfunction "GND_4") (pintype "power_in"))
    )
    (net (code "60") (name "Net-(D1-A)") (class "Default")
      (node (ref "D1") (pin "1") (pinfunction "A_1") (pintype "passive"))
      (node (ref "R9") (pin "2") (pinfunction "2_2") (pintype "passive"))
    )
    (net (code "61") (name "Net-(P14-Pad2)") (class "Default")
      (node (ref "P14") (pin "2") (pinfunction "2_2") (pintype "passive"))
      (node (ref "R15") (pin "2") (pinfunction "2_2") (pintype "passive"))
    )
    (net (code "62") (name "Net-(P14-Pad3)") (class "Default")
      (node (ref "P14") (pin "3") (pinfunction "3_3") (pintype "passive"))
      (node (ref "R8") (pin "2") (pinfunction "2_2") (pintype "passive"))
    )
    (net (code "63") (name "Net-(Q1B-G2)") (class "Default")
      (node (ref "Q1") (pin "4") (pinfunction "G2_4") (pintype "passive"))
      (node (ref "Q3") (pin "3") (pinfunction "20_3") (pintype "passive"))
      (node (ref "R1") (pin "1") (pinfunction "1_1") (pintype "passive"))
    )
    (net (code "64") (name "Net-(Q2B-G2)") (class "Default")
      (node (ref "Q2") (pin "4") (pinfunction "G2_4") (pintype "passive"))
      (node (ref "Q4") (pin "3") (pinfunction "20_3") (pintype "passive"))
      (node (ref "R2") (pin "1") (pinfunction "1_1") (pintype "passive"))
    )
    (net (code "65") (name "Net-(Q5B-G2)") (class "Default")
      (node (ref "Q5") (pin "4") (pinfunction "G2_4") (pintype "passive"))
      (node (ref "Q7") (pin "3") (pinfunction "20_3") (pintype "passive"))
      (node (ref "R3") (pin "1") (pinfunction "1_1") (pintype "passive"))
    )
    (net (code "66") (name "Net-(Q6B-G2)") (class "Default")
      (node (ref "Q6") (pin "4") (pinfunction "G2_4") (pintype "passive"))
      (node (ref "Q8") (pin "3") (pinfunction "20_3") (pintype "passive"))
      (node (ref "R4") (pin "1") (pinfunction "1_1") (pintype "passive"))
    )
    (net (code "67") (name "Net-(Q10B-G2)") (class "Default")
      (node (ref "Q10") (pin "4") (pinfunction "G2_4") (pintype "passive"))
      (node (ref "Q12") (pin "3") (pinfunction "20_3") (pintype "passive"))
      (node (ref "R7") (pin "1") (pinfunction "1_1") (pintype "passive"))
    )
    (net (code "68") (name "Net-(Q11-20)") (class "Default")
      (node (ref "Q11") (pin "3") (pinfunction "20_3") (pintype "passive"))
      (node (ref "Q9") (pin "4") (pinfunction "G2_4") (pintype "passive"))
      (node (ref "R6") (pin "1") (pinfunction "1_1") (pintype "passive"))
    )
    (net (code "69") (name "Net-(Q13B-G2)") (class "Default")
      (node (ref "Q13") (pin "4") (pinfunction "G2_4") (pintype "passive"))
      (node (ref "Q14") (pin "3") (pinfunction "20_3") (pintype "passive"))
      (node (ref "R10") (pin "1") (pinfunction "1_1") (pintype "passive"))
    )
    (net (code "70") (name "Net-(Q15B-G2)") (class "Default")
      (node (ref "Q15") (pin "4") (pinfunction "G2_4") (pintype "passive"))
      (node (ref "Q16") (pin "3") (pinfunction "20_3") (pintype "passive"))
      (node (ref "R11") (pin "1") (pinfunction "1_1") (pintype "passive"))
    )
    (net (code "71") (name "Net-(Q17B-G2)") (class "Default")
      (node (ref "Q17") (pin "4") (pinfunction "G2_4") (pintype "passive"))
      (node (ref "Q18") (pin "3") (pinfunction "20_3") (pintype "passive"))
      (node (ref "R12") (pin "1") (pinfunction "1_1") (pintype "passive"))
    )
    (net (code "72") (name "Net-(U1-OSC_IN{slash}PD0)") (class "Default")
      (node (ref "C1") (pin "1") (pinfunction "1_1") (pintype "passive"))
      (node (ref "U1") (pin "5") (pinfunction "OSC_IN/PD0_5") (pintype "input"))
      (node (ref "Y1") (pin "1") (pinfunction "1_1") (pintype "passive"))
    )
    (net (code "73") (name "Net-(U1-OSC_OUT{slash}PD1)") (class "Default")
      (node (ref "C2") (pin "1") (pinfunction "1_1") (pintype "passive"))
      (node (ref "U1") (pin "6") (pinfunction "OSC_OUT/PD1_6") (pintype "output"))
      (node (ref "Y1") (pin "2") (pinfunction "2_2") (pintype "passive"))
    )
    (net (code "74") (name "unconnected-(J1-GND-Pad4)") (class "Default")
      (node (ref "J1") (pin "4") (pinfunction "GND_4") (pintype "power_in"))
    )
    (net (code "75") (name "unconnected-(U1-PC9-Pad40)") (class "Default")
      (node (ref "U1") (pin "40") (pinfunction "PC9_40") (pintype "bidirectional"))
    )
    (net (code "76") (name "unconnected-(U1-PC13-TAMPER-RTC-Pad2)") (class "Default")
      (node (ref "U1") (pin "2") (pinfunction "PC13-TAMPER-RTC_2") (pintype "bidirectional"))
    )
    (net (code "77") (name "unconnected-(U1-PC14-OSC32_IN-Pad3)") (class "Default")
      (node (ref "U1") (pin "3") (pinfunction "PC14-OSC32_IN_3") (pintype "bidirectional"))
    )
    (net (code "78") (name "unconnected-(U1-PC15-OSC32_OUT-Pad4)") (class "Default")
      (node (ref "U1") (pin "4") (pinfunction "PC15-OSC32_OUT_4") (pintype "bidirectional"))
    )
  )
)
